# Controller_v4.net
KiCad netlist of a schematic drawn in EAGLE
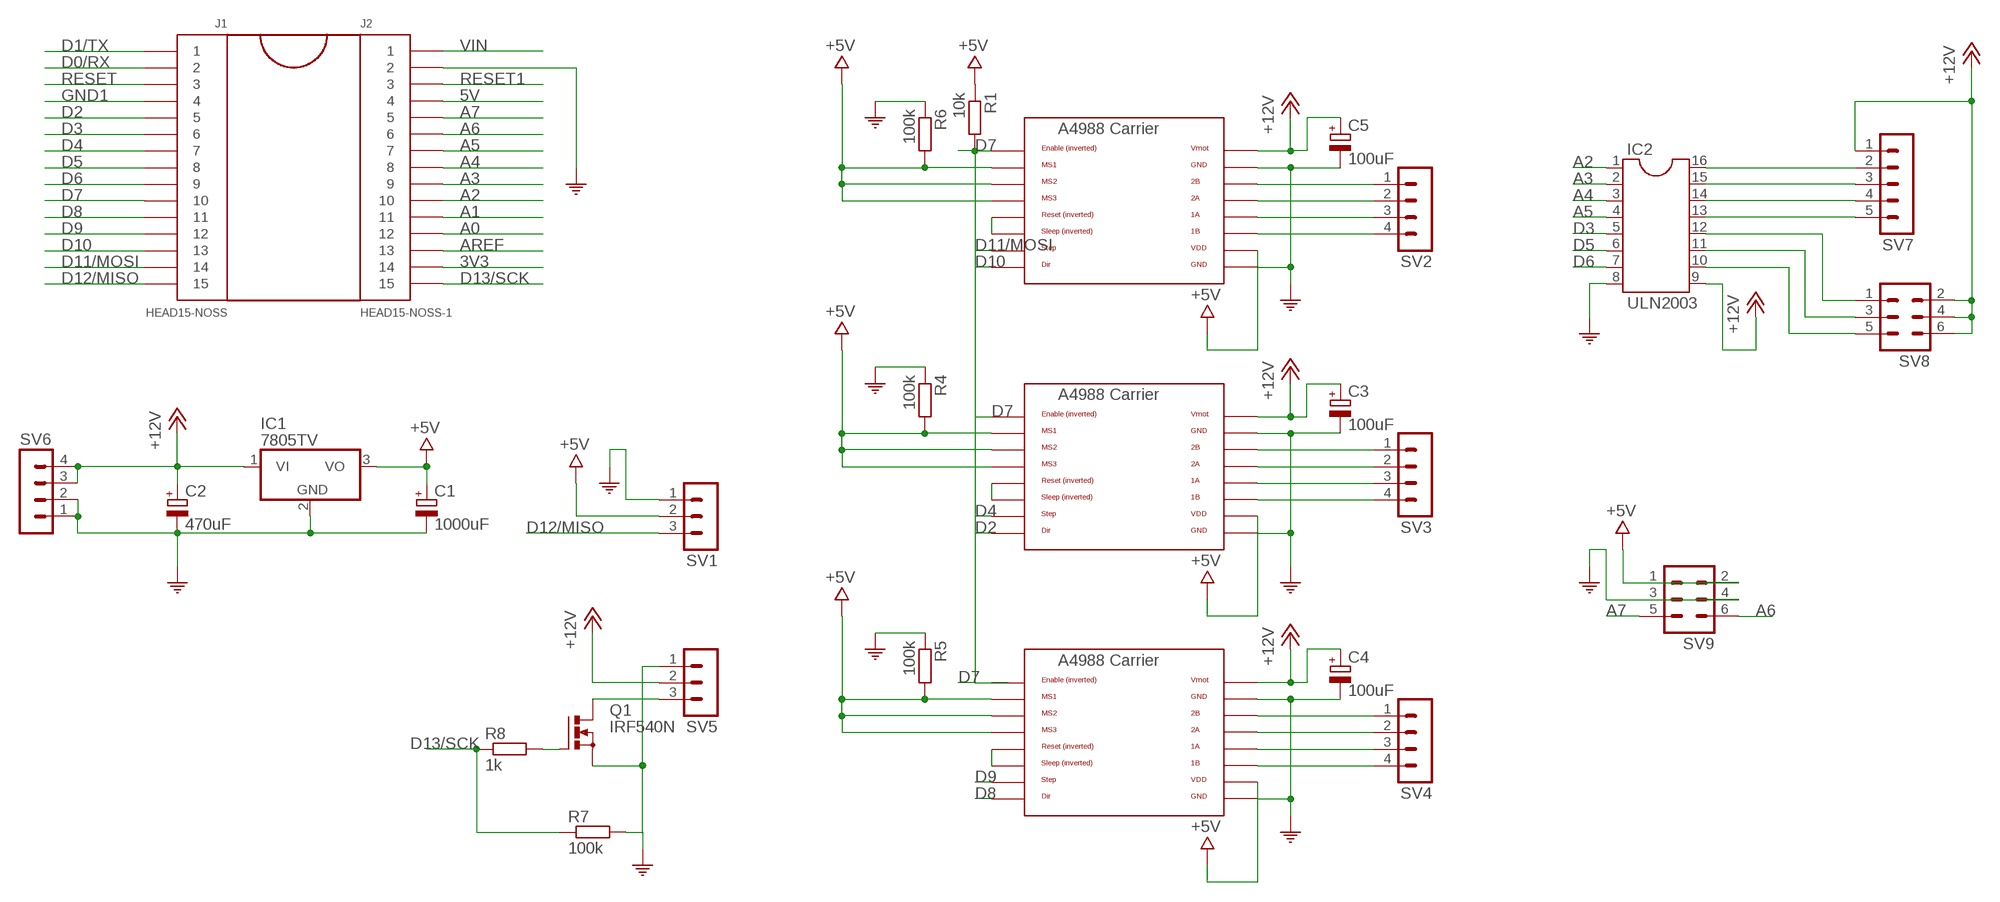
[diagram p0: schematic, sheet 1]

(export (version "E")
  (design (tool "Eeschema 10.0.6"))
  (components
    (comp (ref "C1")
      (value "1000uF")
      (footprint "eagle-import:TAP5-70")
      (libsource (lib "eagle-import") (part "CPOL-EUTAP5-70"))
    )
    (comp (ref "C2")
      (value "470uF")
      (footprint "eagle-import:TAP5-70")
      (libsource (lib "eagle-import") (part "CPOL-EUTAP5-70"))
    )
    (comp (ref "C3")
      (value "100uF")
      (footprint "eagle-import:TAP5-70")
      (libsource (lib "eagle-import") (part "CPOL-EUTAP5-70"))
    )
    (comp (ref "C4")
      (value "100uF")
      (footprint "eagle-import:TAP5-70")
      (libsource (lib "eagle-import") (part "CPOL-EUTAP5-70"))
    )
    (comp (ref "C5")
      (value "100uF")
      (footprint "eagle-import:TAP5-70")
      (libsource (lib "eagle-import") (part "CPOL-EUTAP5-70"))
    )
    (comp (ref "IC1")
      (value "7805TV")
      (footprint "eagle-import:TO220V")
      (libsource (lib "eagle-import") (part "78TV05"))
    )
    (comp (ref "IC2")
      (value "ULN2003")
      (footprint "eagle-import:DIL16")
      (libsource (lib "eagle-import") (part "DIL16"))
    )
    (comp (ref "J1")
      (value "HEAD15-NOSS")
      (footprint "eagle-import:HEAD15-NOSS")
      (libsource (lib "eagle-import") (part "HEAD15-NOSS"))
    )
    (comp (ref "J2")
      (value "HEAD15-NOSS-1")
      (footprint "eagle-import:HEAD15-NOSS-1")
      (libsource (lib "eagle-import") (part "HEAD15-NOSS-1"))
    )
    (comp (ref "Q1")
      (value "IRF540N")
      (footprint "eagle-import:TO220BV")
      (libsource (lib "eagle-import") (part "PMOSFET_NTO220BV"))
    )
    (comp (ref "R1")
      (value "10k")
      (footprint "eagle-import:0207_10")
      (libsource (lib "eagle-import") (part "R-EU_0207/10"))
    )
    (comp (ref "R4")
      (value "100k")
      (footprint "eagle-import:0207_10")
      (libsource (lib "eagle-import") (part "R-EU_0207/10"))
    )
    (comp (ref "R5")
      (value "100k")
      (footprint "eagle-import:0207_10")
      (libsource (lib "eagle-import") (part "R-EU_0207/10"))
    )
    (comp (ref "R6")
      (value "100k")
      (footprint "eagle-import:0207_10")
      (libsource (lib "eagle-import") (part "R-EU_0207/10"))
    )
    (comp (ref "R7")
      (value "100k")
      (footprint "eagle-import:0207_10")
      (libsource (lib "eagle-import") (part "R-EU_0207/10"))
    )
    (comp (ref "R8")
      (value "1k")
      (footprint "eagle-import:0207_10")
      (libsource (lib "eagle-import") (part "R-EU_0207/10"))
    )
    (comp (ref "SV1")
      (value "MA03-1")
      (footprint "eagle-import:MA03-1")
      (libsource (lib "eagle-import") (part "MA03-1"))
    )
    (comp (ref "SV2")
      (value "MA04-1")
      (footprint "eagle-import:MA04-1")
      (libsource (lib "eagle-import") (part "MA04-1"))
    )
    (comp (ref "SV3")
      (value "MA04-1")
      (footprint "eagle-import:MA04-1")
      (libsource (lib "eagle-import") (part "MA04-1"))
    )
    (comp (ref "SV4")
      (value "MA04-1")
      (footprint "eagle-import:MA04-1")
      (libsource (lib "eagle-import") (part "MA04-1"))
    )
    (comp (ref "SV5")
      (value "MA03-1")
      (footprint "eagle-import:MA03-1")
      (libsource (lib "eagle-import") (part "MA03-1"))
    )
    (comp (ref "SV6")
      (value "MA04-1")
      (footprint "eagle-import:MA04-1")
      (libsource (lib "eagle-import") (part "MA04-1"))
    )
    (comp (ref "SV7")
      (value "MA05-1")
      (footprint "eagle-import:MA05-1")
      (libsource (lib "eagle-import") (part "MA05-1"))
    )
    (comp (ref "SV8")
      (value "MA03-2")
      (footprint "eagle-import:MA03-2")
      (libsource (lib "eagle-import") (part "MA03-2"))
    )
    (comp (ref "SV9")
      (value "MA03-2")
      (footprint "eagle-import:MA03-2")
      (libsource (lib "eagle-import") (part "MA03-2"))
    )
    (comp (ref "U$3")
      (value "A4988BREAKOUT")
      (footprint "eagle-import:A4988BREAKOUT")
      (libsource (lib "eagle-import") (part "A4988BREAKOUT"))
    )
    (comp (ref "U$4")
      (value "A4988BREAKOUT")
      (footprint "eagle-import:A4988BREAKOUT")
      (libsource (lib "eagle-import") (part "A4988BREAKOUT"))
    )
    (comp (ref "U$5")
      (value "A4988BREAKOUT")
      (footprint "eagle-import:A4988BREAKOUT")
      (libsource (lib "eagle-import") (part "A4988BREAKOUT"))
    )
  )
  (nets
    (net (code "1") (name "+5V") (class "Default")
      (node (ref "C1") (pin "+") (pinfunction "+_+") (pintype "passive"))
      (node (ref "IC1") (pin "3") (pinfunction "VO_3") (pintype "passive"))
      (node (ref "R1") (pin "1") (pinfunction "1_1") (pintype "passive"))
      (node (ref "R4") (pin "2") (pinfunction "2_2") (pintype "passive"))
      (node (ref "R5") (pin "2") (pinfunction "2_2") (pintype "passive"))
      (node (ref "R6") (pin "2") (pinfunction "2_2") (pintype "passive"))
      (node (ref "SV1") (pin "2") (pinfunction "2_2") (pintype "passive"))
      (node (ref "SV9") (pin "1") (pinfunction "1_1") (pintype "passive"))
      (node (ref "SV9") (pin "2") (pinfunction "2_2") (pintype "passive"))
      (node (ref "U$3") (pin "MS1") (pinfunction "MS1_MS1") (pintype "input"))
      (node (ref "U$3") (pin "MS2") (pinfunction "MS2_MS2") (pintype "input"))
      (node (ref "U$3") (pin "MS3") (pinfunction "MS3_MS3") (pintype "input"))
      (node (ref "U$3") (pin "VDD") (pinfunction "VDD_VDD") (pintype "power_in"))
      (node (ref "U$4") (pin "MS1") (pinfunction "MS1_MS1") (pintype "input"))
      (node (ref "U$4") (pin "MS2") (pinfunction "MS2_MS2") (pintype "input"))
      (node (ref "U$4") (pin "MS3") (pinfunction "MS3_MS3") (pintype "input"))
      (node (ref "U$4") (pin "VDD") (pinfunction "VDD_VDD") (pintype "power_in"))
      (node (ref "U$5") (pin "MS1") (pinfunction "MS1_MS1") (pintype "input"))
      (node (ref "U$5") (pin "MS2") (pinfunction "MS2_MS2") (pintype "input"))
      (node (ref "U$5") (pin "MS3") (pinfunction "MS3_MS3") (pintype "input"))
      (node (ref "U$5") (pin "VDD") (pinfunction "VDD_VDD") (pintype "power_in"))
    )
    (net (code "2") (name "+12V") (class "Default")
      (node (ref "C2") (pin "+") (pinfunction "+_+") (pintype "passive"))
      (node (ref "C3") (pin "+") (pinfunction "+_+") (pintype "passive"))
      (node (ref "C4") (pin "+") (pinfunction "+_+") (pintype "passive"))
      (node (ref "C5") (pin "+") (pinfunction "+_+") (pintype "passive"))
      (node (ref "IC1") (pin "1") (pinfunction "VI_1") (pintype "input"))
      (node (ref "IC2") (pin "9") (pinfunction "9_9") (pintype "passive"))
      (node (ref "SV5") (pin "2") (pinfunction "2_2") (pintype "passive"))
      (node (ref "SV6") (pin "3") (pinfunction "3_3") (pintype "passive"))
      (node (ref "SV6") (pin "4") (pinfunction "4_4") (pintype "passive"))
      (node (ref "SV7") (pin "1") (pinfunction "1_1") (pintype "passive"))
      (node (ref "SV8") (pin "2") (pinfunction "2_2") (pintype "passive"))
      (node (ref "SV8") (pin "4") (pinfunction "4_4") (pintype "passive"))
      (node (ref "SV8") (pin "6") (pinfunction "6_6") (pintype "passive"))
      (node (ref "U$3") (pin "VMOT") (pinfunction "VMOT_VMOT") (pintype "power_in"))
      (node (ref "U$4") (pin "VMOT") (pinfunction "VMOT_VMOT") (pintype "power_in"))
      (node (ref "U$5") (pin "VMOT") (pinfunction "VMOT_VMOT") (pintype "power_in"))
    )
    (net (code "3") (name "/3V3") (class "Default")
      (node (ref "J2") (pin "14") (pinfunction "14_14") (pintype "passive"))
    )
    (net (code "4") (name "/5V") (class "Default")
      (node (ref "J2") (pin "4") (pinfunction "4_4") (pintype "passive"))
    )
    (net (code "5") (name "/A0") (class "Default")
      (node (ref "J2") (pin "12") (pinfunction "12_12") (pintype "passive"))
    )
    (net (code "6") (name "/A1") (class "Default")
      (node (ref "J2") (pin "11") (pinfunction "11_11") (pintype "passive"))
    )
    (net (code "7") (name "/A2") (class "Default")
      (node (ref "IC2") (pin "1") (pinfunction "1_1") (pintype "passive"))
      (node (ref "J2") (pin "10") (pinfunction "10_10") (pintype "passive"))
    )
    (net (code "8") (name "/A3") (class "Default")
      (node (ref "IC2") (pin "2") (pinfunction "2_2") (pintype "passive"))
      (node (ref "J2") (pin "9") (pinfunction "9_9") (pintype "passive"))
    )
    (net (code "9") (name "/A4") (class "Default")
      (node (ref "IC2") (pin "3") (pinfunction "3_3") (pintype "passive"))
      (node (ref "J2") (pin "8") (pinfunction "8_8") (pintype "passive"))
    )
    (net (code "10") (name "/A5") (class "Default")
      (node (ref "IC2") (pin "4") (pinfunction "4_4") (pintype "passive"))
      (node (ref "J2") (pin "7") (pinfunction "7_7") (pintype "passive"))
    )
    (net (code "11") (name "/A6") (class "Default")
      (node (ref "J2") (pin "6") (pinfunction "6_6") (pintype "passive"))
      (node (ref "SV9") (pin "6") (pinfunction "6_6") (pintype "passive"))
    )
    (net (code "12") (name "/A7") (class "Default")
      (node (ref "J2") (pin "5") (pinfunction "5_5") (pintype "passive"))
      (node (ref "SV9") (pin "5") (pinfunction "5_5") (pintype "passive"))
    )
    (net (code "13") (name "/AREF") (class "Default")
      (node (ref "J2") (pin "13") (pinfunction "13_13") (pintype "passive"))
    )
    (net (code "14") (name "/D0{slash}RX") (class "Default")
      (node (ref "J1") (pin "2") (pinfunction "2_2") (pintype "passive"))
    )
    (net (code "15") (name "/D1{slash}TX") (class "Default")
      (node (ref "J1") (pin "1") (pinfunction "1_1") (pintype "passive"))
    )
    (net (code "16") (name "/D2") (class "Default")
      (node (ref "J1") (pin "5") (pinfunction "5_5") (pintype "passive"))
      (node (ref "U$5") (pin "DIR") (pinfunction "DIR_DIR") (pintype "input"))
    )
    (net (code "17") (name "/D3") (class "Default")
      (node (ref "IC2") (pin "5") (pinfunction "5_5") (pintype "passive"))
      (node (ref "J1") (pin "6") (pinfunction "6_6") (pintype "passive"))
    )
    (net (code "18") (name "/D4") (class "Default")
      (node (ref "J1") (pin "7") (pinfunction "7_7") (pintype "passive"))
      (node (ref "U$5") (pin "STEP") (pinfunction "STEP_STEP") (pintype "input"))
    )
    (net (code "19") (name "/D5") (class "Default")
      (node (ref "IC2") (pin "6") (pinfunction "6_6") (pintype "passive"))
      (node (ref "J1") (pin "8") (pinfunction "8_8") (pintype "passive"))
    )
    (net (code "20") (name "/D6") (class "Default")
      (node (ref "IC2") (pin "7") (pinfunction "7_7") (pintype "passive"))
      (node (ref "J1") (pin "9") (pinfunction "9_9") (pintype "passive"))
    )
    (net (code "21") (name "/D7") (class "Default")
      (node (ref "J1") (pin "10") (pinfunction "10_10") (pintype "passive"))
      (node (ref "R1") (pin "2") (pinfunction "2_2") (pintype "passive"))
      (node (ref "U$3") (pin "EN") (pinfunction "EN_EN") (pintype "input"))
      (node (ref "U$4") (pin "EN") (pinfunction "EN_EN") (pintype "input"))
      (node (ref "U$5") (pin "EN") (pinfunction "EN_EN") (pintype "input"))
    )
    (net (code "22") (name "/D8") (class "Default")
      (node (ref "J1") (pin "11") (pinfunction "11_11") (pintype "passive"))
      (node (ref "U$4") (pin "DIR") (pinfunction "DIR_DIR") (pintype "input"))
    )
    (net (code "23") (name "/D9") (class "Default")
      (node (ref "J1") (pin "12") (pinfunction "12_12") (pintype "passive"))
      (node (ref "U$4") (pin "STEP") (pinfunction "STEP_STEP") (pintype "input"))
    )
    (net (code "24") (name "/D10") (class "Default")
      (node (ref "J1") (pin "13") (pinfunction "13_13") (pintype "passive"))
      (node (ref "U$3") (pin "DIR") (pinfunction "DIR_DIR") (pintype "input"))
    )
    (net (code "25") (name "/D11{slash}MOSI") (class "Default")
      (node (ref "J1") (pin "14") (pinfunction "14_14") (pintype "passive"))
      (node (ref "U$3") (pin "STEP") (pinfunction "STEP_STEP") (pintype "input"))
    )
    (net (code "26") (name "/D12{slash}MISO") (class "Default")
      (node (ref "J1") (pin "15") (pinfunction "15_15") (pintype "passive"))
      (node (ref "SV1") (pin "3") (pinfunction "3_3") (pintype "passive"))
    )
    (net (code "27") (name "/D13{slash}SCK") (class "Default")
      (node (ref "J2") (pin "15") (pinfunction "15_15") (pintype "passive"))
      (node (ref "R7") (pin "1") (pinfunction "1_1") (pintype "passive"))
      (node (ref "R8") (pin "1") (pinfunction "1_1") (pintype "passive"))
    )
    (net (code "28") (name "/GND1") (class "Default")
      (node (ref "J1") (pin "4") (pinfunction "4_4") (pintype "passive"))
    )
    (net (code "29") (name "/RESET") (class "Default")
      (node (ref "J1") (pin "3") (pinfunction "3_3") (pintype "passive"))
    )
    (net (code "30") (name "/RESET1") (class "Default")
      (node (ref "J2") (pin "3") (pinfunction "3_3") (pintype "passive"))
    )
    (net (code "31") (name "/VIN") (class "Default")
      (node (ref "J2") (pin "1") (pinfunction "1_1") (pintype "passive"))
    )
    (net (code "32") (name "COM") (class "Default")
      (node (ref "C1") (pin "-") (pinfunction "-_-") (pintype "passive"))
      (node (ref "C2") (pin "-") (pinfunction "-_-") (pintype "passive"))
      (node (ref "C3") (pin "-") (pinfunction "-_-") (pintype "passive"))
      (node (ref "C4") (pin "-") (pinfunction "-_-") (pintype "passive"))
      (node (ref "C5") (pin "-") (pinfunction "-_-") (pintype "passive"))
      (node (ref "IC1") (pin "2") (pinfunction "GND_2") (pintype "passive"))
      (node (ref "IC2") (pin "8") (pinfunction "8_8") (pintype "passive"))
      (node (ref "J2") (pin "2") (pinfunction "2_2") (pintype "passive"))
      (node (ref "Q1") (pin "S") (pinfunction "S_S") (pintype "passive"))
      (node (ref "R4") (pin "1") (pinfunction "1_1") (pintype "passive"))
      (node (ref "R5") (pin "1") (pinfunction "1_1") (pintype "passive"))
      (node (ref "R6") (pin "1") (pinfunction "1_1") (pintype "passive"))
      (node (ref "R7") (pin "2") (pinfunction "2_2") (pintype "passive"))
      (node (ref "SV1") (pin "1") (pinfunction "1_1") (pintype "passive"))
      (node (ref "SV5") (pin "1") (pinfunction "1_1") (pintype "passive"))
      (node (ref "SV6") (pin "1") (pinfunction "1_1") (pintype "passive"))
      (node (ref "SV6") (pin "2") (pinfunction "2_2") (pintype "passive"))
      (node (ref "SV9") (pin "3") (pinfunction "3_3") (pintype "passive"))
      (node (ref "SV9") (pin "4") (pinfunction "4_4") (pintype "passive"))
      (node (ref "U$3") (pin "GND") (pinfunction "GND_GND") (pintype "power_in"))
      (node (ref "U$3") (pin "GND@0") (pinfunction "GND_GND@0") (pintype "power_in"))
      (node (ref "U$4") (pin "GND") (pinfunction "GND_GND") (pintype "power_in"))
      (node (ref "U$4") (pin "GND@0") (pinfunction "GND_GND@0") (pintype "power_in"))
      (node (ref "U$5") (pin "GND") (pinfunction "GND_GND") (pintype "power_in"))
      (node (ref "U$5") (pin "GND@0") (pinfunction "GND_GND@0") (pintype "power_in"))
    )
    (net (code "33") (name "Net-(IC2-Pad10)") (class "Default")
      (node (ref "IC2") (pin "10") (pinfunction "10_10") (pintype "passive"))
      (node (ref "SV8") (pin "5") (pinfunction "5_5") (pintype "passive"))
    )
    (net (code "34") (name "Net-(IC2-Pad11)") (class "Default")
      (node (ref "IC2") (pin "11") (pinfunction "11_11") (pintype "passive"))
      (node (ref "SV8") (pin "3") (pinfunction "3_3") (pintype "passive"))
    )
    (net (code "35") (name "Net-(IC2-Pad12)") (class "Default")
      (node (ref "IC2") (pin "12") (pinfunction "12_12") (pintype "passive"))
      (node (ref "SV8") (pin "1") (pinfunction "1_1") (pintype "passive"))
    )
    (net (code "36") (name "Net-(IC2-Pad13)") (class "Default")
      (node (ref "IC2") (pin "13") (pinfunction "13_13") (pintype "passive"))
      (node (ref "SV7") (pin "5") (pinfunction "5_5") (pintype "passive"))
    )
    (net (code "37") (name "Net-(IC2-Pad14)") (class "Default")
      (node (ref "IC2") (pin "14") (pinfunction "14_14") (pintype "passive"))
      (node (ref "SV7") (pin "4") (pinfunction "4_4") (pintype "passive"))
    )
    (net (code "38") (name "Net-(IC2-Pad15)") (class "Default")
      (node (ref "IC2") (pin "15") (pinfunction "15_15") (pintype "passive"))
      (node (ref "SV7") (pin "3") (pinfunction "3_3") (pintype "passive"))
    )
    (net (code "39") (name "Net-(IC2-Pad16)") (class "Default")
      (node (ref "IC2") (pin "16") (pinfunction "16_16") (pintype "passive"))
      (node (ref "SV7") (pin "2") (pinfunction "2_2") (pintype "passive"))
    )
    (net (code "40") (name "Net-(Q1-PadD)") (class "Default")
      (node (ref "Q1") (pin "D") (pinfunction "D_D") (pintype "passive"))
      (node (ref "SV5") (pin "3") (pinfunction "3_3") (pintype "passive"))
    )
    (net (code "41") (name "Net-(Q1-PadG)") (class "Default")
      (node (ref "Q1") (pin "G") (pinfunction "G_G") (pintype "passive"))
      (node (ref "R8") (pin "2") (pinfunction "2_2") (pintype "passive"))
    )
    (net (code "42") (name "Net-(SV2-Pad1)") (class "Default")
      (node (ref "SV2") (pin "1") (pinfunction "1_1") (pintype "passive"))
      (node (ref "U$3") (pin "2B") (pinfunction "2B_2B") (pintype "output"))
    )
    (net (code "43") (name "Net-(SV2-Pad2)") (class "Default")
      (node (ref "SV2") (pin "2") (pinfunction "2_2") (pintype "passive"))
      (node (ref "U$3") (pin "2A") (pinfunction "2A_2A") (pintype "output"))
    )
    (net (code "44") (name "Net-(SV2-Pad3)") (class "Default")
      (node (ref "SV2") (pin "3") (pinfunction "3_3") (pintype "passive"))
      (node (ref "U$3") (pin "1A") (pinfunction "1A_1A") (pintype "output"))
    )
    (net (code "45") (name "Net-(SV2-Pad4)") (class "Default")
      (node (ref "SV2") (pin "4") (pinfunction "4_4") (pintype "passive"))
      (node (ref "U$3") (pin "1B") (pinfunction "1B_1B") (pintype "output"))
    )
    (net (code "46") (name "Net-(SV3-Pad1)") (class "Default")
      (node (ref "SV3") (pin "1") (pinfunction "1_1") (pintype "passive"))
      (node (ref "U$5") (pin "2B") (pinfunction "2B_2B") (pintype "output"))
    )
    (net (code "47") (name "Net-(SV3-Pad2)") (class "Default")
      (node (ref "SV3") (pin "2") (pinfunction "2_2") (pintype "passive"))
      (node (ref "U$5") (pin "2A") (pinfunction "2A_2A") (pintype "output"))
    )
    (net (code "48") (name "Net-(SV3-Pad3)") (class "Default")
      (node (ref "SV3") (pin "3") (pinfunction "3_3") (pintype "passive"))
      (node (ref "U$5") (pin "1A") (pinfunction "1A_1A") (pintype "output"))
    )
    (net (code "49") (name "Net-(SV3-Pad4)") (class "Default")
      (node (ref "SV3") (pin "4") (pinfunction "4_4") (pintype "passive"))
      (node (ref "U$5") (pin "1B") (pinfunction "1B_1B") (pintype "output"))
    )
    (net (code "50") (name "Net-(SV4-Pad1)") (class "Default")
      (node (ref "SV4") (pin "1") (pinfunction "1_1") (pintype "passive"))
      (node (ref "U$4") (pin "2B") (pinfunction "2B_2B") (pintype "output"))
    )
    (net (code "51") (name "Net-(SV4-Pad2)") (class "Default")
      (node (ref "SV4") (pin "2") (pinfunction "2_2") (pintype "passive"))
      (node (ref "U$4") (pin "2A") (pinfunction "2A_2A") (pintype "output"))
    )
    (net (code "52") (name "Net-(SV4-Pad3)") (class "Default")
      (node (ref "SV4") (pin "3") (pinfunction "3_3") (pintype "passive"))
      (node (ref "U$4") (pin "1A") (pinfunction "1A_1A") (pintype "output"))
    )
    (net (code "53") (name "Net-(SV4-Pad4)") (class "Default")
      (node (ref "SV4") (pin "4") (pinfunction "4_4") (pintype "passive"))
      (node (ref "U$4") (pin "1B") (pinfunction "1B_1B") (pintype "output"))
    )
    (net (code "54") (name "Net-(U$3-SLEEP)") (class "Default")
      (node (ref "U$3") (pin "RST") (pinfunction "RST_RST") (pintype "input"))
      (node (ref "U$3") (pin "SLP") (pinfunction "SLEEP_SLP") (pintype "input"))
    )
    (net (code "55") (name "Net-(U$4-SLEEP)") (class "Default")
      (node (ref "U$4") (pin "RST") (pinfunction "RST_RST") (pintype "input"))
      (node (ref "U$4") (pin "SLP") (pinfunction "SLEEP_SLP") (pintype "input"))
    )
    (net (code "56") (name "Net-(U$5-SLEEP)") (class "Default")
      (node (ref "U$5") (pin "RST") (pinfunction "RST_RST") (pintype "input"))
      (node (ref "U$5") (pin "SLP") (pinfunction "SLEEP_SLP") (pintype "input"))
    )
  )
)
